# Qwiic_PT100.net
KiCad netlist of a schematic drawn in EAGLE
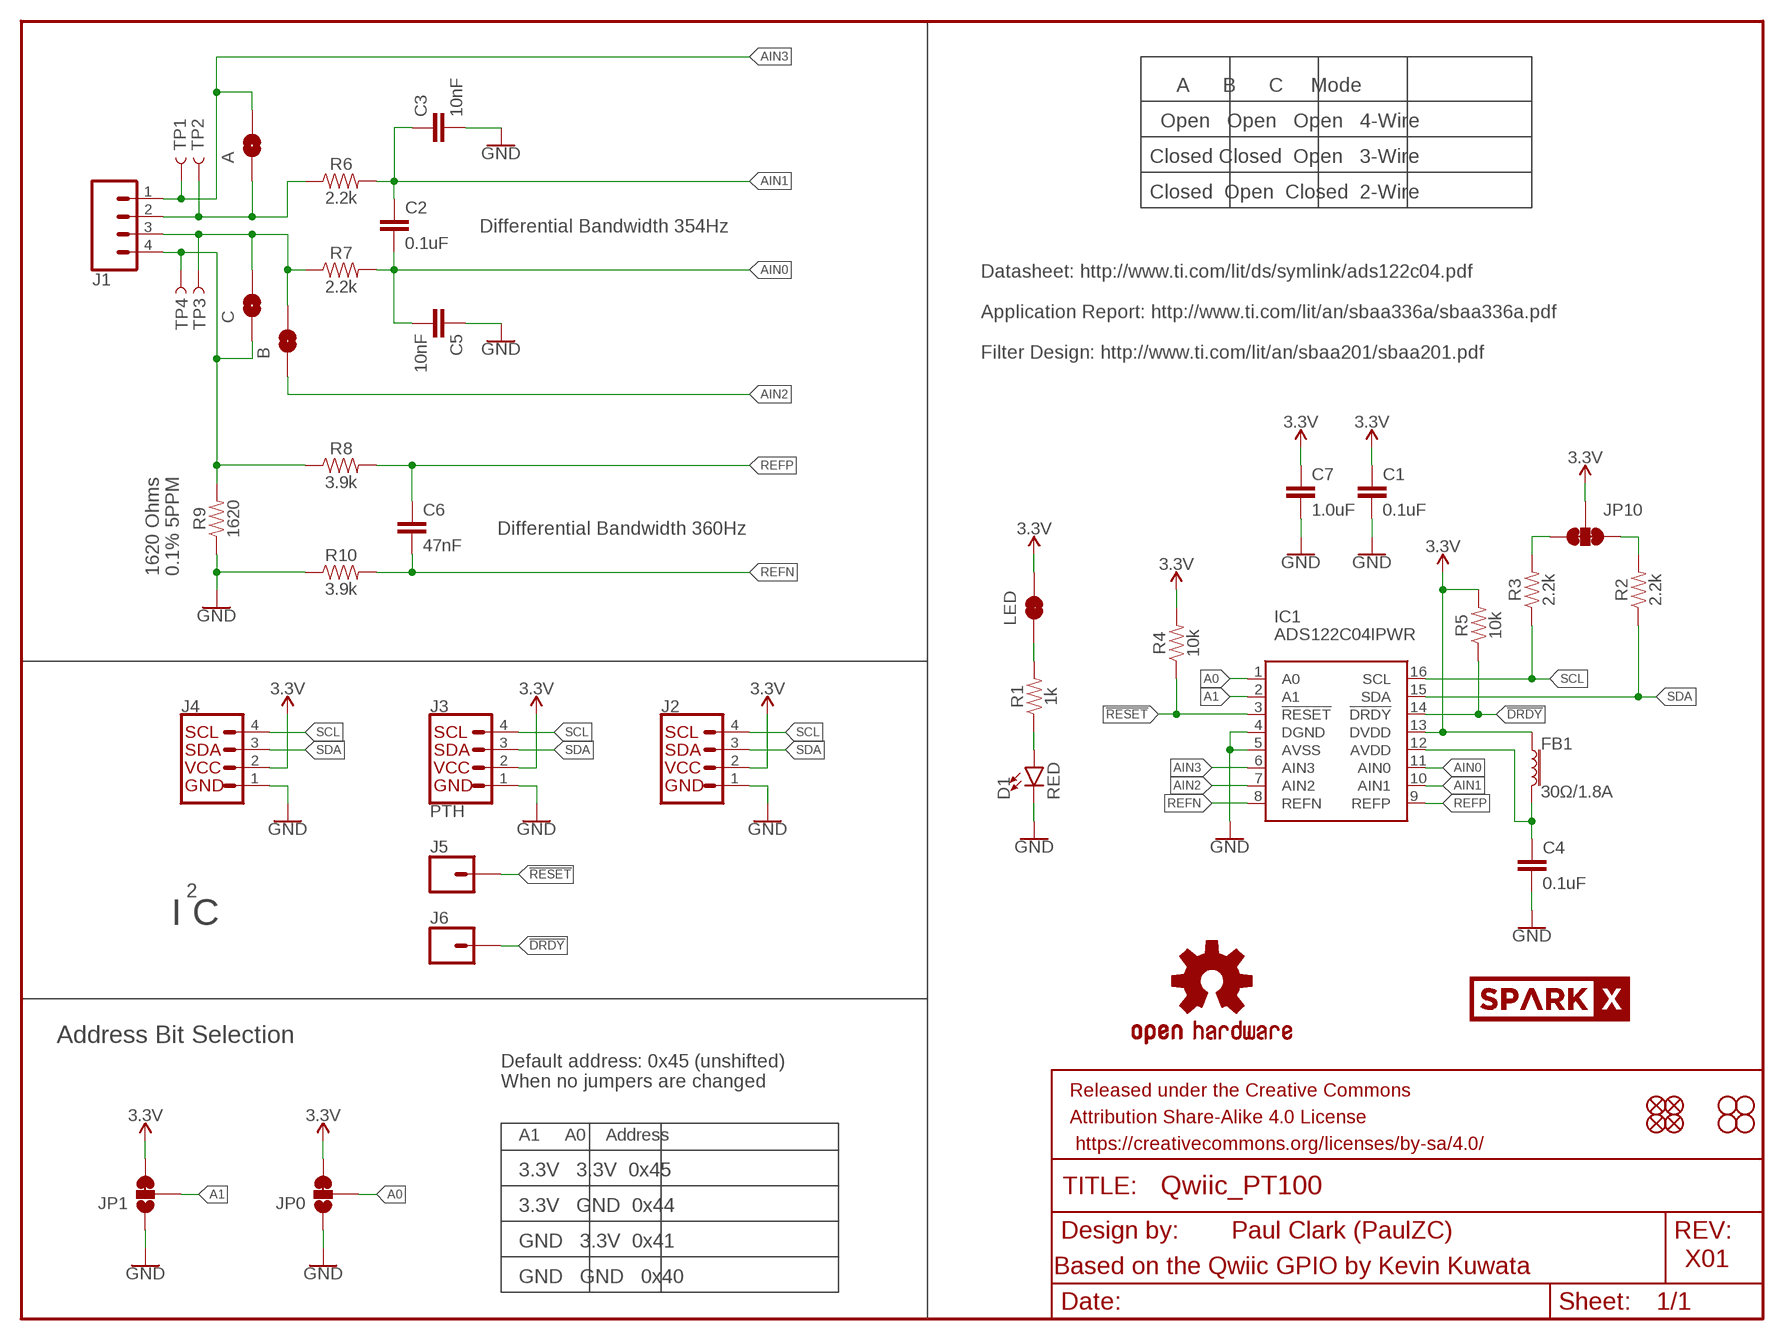
[diagram p0: schematic, sheet 1]

(export (version "E")
  (design (tool "Eeschema 10.0.6"))
  (components
    (comp (ref "A")
      (value "JUMPER-SMT_2_NO_SILK_ROUND")
      (footprint "eagle-import:SMT-JUMPER_2_NO_SILK_ROUND")
      (libsource (lib "eagle-import") (part "JUMPER-SMT_2_NO_SILK_ROUND"))
    )
    (comp (ref "B")
      (value "JUMPER-SMT_2_NO_SILK_ROUND")
      (footprint "eagle-import:SMT-JUMPER_2_NO_SILK_ROUND")
      (libsource (lib "eagle-import") (part "JUMPER-SMT_2_NO_SILK_ROUND"))
    )
    (comp (ref "C")
      (value "JUMPER-SMT_2_NO_SILK_ROUND")
      (footprint "eagle-import:SMT-JUMPER_2_NO_SILK_ROUND")
      (libsource (lib "eagle-import") (part "JUMPER-SMT_2_NO_SILK_ROUND"))
    )
    (comp (ref "C1")
      (value "0.1uF")
      (footprint "eagle-import:0603")
      (libsource (lib "eagle-import") (part "0.1UF-0603-25V-(+80/-20%)"))
    )
    (comp (ref "C2")
      (value "0.1uF")
      (footprint "eagle-import:0603")
      (libsource (lib "eagle-import") (part "0.1UF-0603-25V-5%"))
    )
    (comp (ref "C3")
      (value "10nF")
      (footprint "eagle-import:0603")
      (libsource (lib "eagle-import") (part "10NF-0603-50V-10%"))
    )
    (comp (ref "C4")
      (value "0.1uF")
      (footprint "eagle-import:0603")
      (libsource (lib "eagle-import") (part "0.1UF-0603-25V-(+80/-20%)"))
    )
    (comp (ref "C5")
      (value "10nF")
      (footprint "eagle-import:0603")
      (libsource (lib "eagle-import") (part "10NF-0603-50V-10%"))
    )
    (comp (ref "C6")
      (value "47nF")
      (footprint "eagle-import:0603")
      (libsource (lib "eagle-import") (part "47NF-0603-25V-5%"))
    )
    (comp (ref "C7")
      (value "1.0uF")
      (footprint "eagle-import:0603")
      (libsource (lib "eagle-import") (part "1.0UF-0603-16V-10%-X7R"))
    )
    (comp (ref "D1")
      (value "RED")
      (footprint "eagle-import:LED-0603")
      (libsource (lib "eagle-import") (part "LED-RED0603"))
    )
    (comp (ref "FB1")
      (value "30Ω/1.8A")
      (footprint "eagle-import:0603")
      (libsource (lib "eagle-import") (part "FERRITE_BEAD-0603"))
    )
    (comp (ref "FD1")
      (value "FIDUCIAL1X2")
      (footprint "eagle-import:FIDUCIAL-1X2")
      (libsource (lib "eagle-import") (part "FIDUCIAL1X2"))
    )
    (comp (ref "FD2")
      (value "FIDUCIAL1X2")
      (footprint "eagle-import:FIDUCIAL-1X2")
      (libsource (lib "eagle-import") (part "FIDUCIAL1X2"))
    )
    (comp (ref "FRAME1")
      (value "FRAME-LETTER")
      (footprint "eagle-import:CREATIVE_COMMONS")
      (libsource (lib "eagle-import") (part "FRAME-LETTER"))
    )
    (comp (ref "H1")
      (value "STAND-OFF")
      (footprint "eagle-import:STAND-OFF")
      (libsource (lib "eagle-import") (part "STAND-OFF"))
    )
    (comp (ref "H2")
      (value "STAND-OFF")
      (footprint "eagle-import:STAND-OFF")
      (libsource (lib "eagle-import") (part "STAND-OFF"))
    )
    (comp (ref "IC1")
      (value "ADS122C04IPWR")
      (footprint "eagle-import:SOP65P640X120-16N")
      (fields (field (name "MOUSER_PART_NUMBER") "595-ADS122C04IPWR"))
      (libsource (lib "eagle-import") (part "ADS122C04IPWR"))
    )
    (comp (ref "J1")
      (value "CONN_04LATCH")
      (footprint "eagle-import:LATCHTERMINAL-5MM-4")
      (fields (field (name "PROD_ID") "CON-14722"))
      (libsource (lib "eagle-import") (part "CONN_04LATCH"))
    )
    (comp (ref "J2")
      (value "QWIIC_RIGHT_ANGLE")
      (footprint "eagle-import:JST04_1MM_RA")
      (fields (field (name "PROD_ID") "CONN-13694"))
      (libsource (lib "eagle-import") (part "QWIIC_CONNECTORJS-1MM"))
    )
    (comp (ref "J3")
      (value "PTH")
      (footprint "eagle-import:1X04_NO_SILK")
      (libsource (lib "eagle-import") (part "I2C_STANDARD_NO_SILK"))
    )
    (comp (ref "J4")
      (value "QWIIC_RIGHT_ANGLE")
      (footprint "eagle-import:JST04_1MM_RA")
      (fields (field (name "PROD_ID") "CONN-13694"))
      (libsource (lib "eagle-import") (part "QWIIC_CONNECTORJS-1MM"))
    )
    (comp (ref "J5")
      (value "CONN_01PTH_NO_SILK_YES_STOP")
      (footprint "eagle-import:1X01_NO_SILK")
      (libsource (lib "eagle-import") (part "CONN_01PTH_NO_SILK_YES_STOP"))
    )
    (comp (ref "J6")
      (value "CONN_01PTH_NO_SILK_YES_STOP")
      (footprint "eagle-import:1X01_NO_SILK")
      (libsource (lib "eagle-import") (part "CONN_01PTH_NO_SILK_YES_STOP"))
    )
    (comp (ref "JP0")
      (value "JUMPER-SMT_3_1-NC_TRACE_SILK")
      (footprint "eagle-import:SMT-JUMPER_3_1-NC_TRACE_SILK")
      (libsource (lib "eagle-import") (part "JUMPER-SMT_3_1-NC_TRACE_SILK"))
    )
    (comp (ref "JP1")
      (value "JUMPER-SMT_3_1-NC_TRACE_SILK")
      (footprint "eagle-import:SMT-JUMPER_3_1-NC_TRACE_SILK")
      (libsource (lib "eagle-import") (part "JUMPER-SMT_3_1-NC_TRACE_SILK"))
    )
    (comp (ref "JP2")
      (value "FIDUCIAL1X2")
      (footprint "eagle-import:FIDUCIAL-1X2")
      (libsource (lib "eagle-import") (part "FIDUCIAL1X2"))
    )
    (comp (ref "JP3")
      (value "STAND-OFF")
      (footprint "eagle-import:STAND-OFF")
      (libsource (lib "eagle-import") (part "STAND-OFF"))
    )
    (comp (ref "JP4")
      (value "STAND-OFF")
      (footprint "eagle-import:STAND-OFF")
      (libsource (lib "eagle-import") (part "STAND-OFF"))
    )
    (comp (ref "JP6")
      (value "FIDUCIAL1X2")
      (footprint "eagle-import:FIDUCIAL-1X2")
      (libsource (lib "eagle-import") (part "FIDUCIAL1X2"))
    )
    (comp (ref "JP10")
      (value "JUMPER-SMT_3_2-NC_TRACE_SILK")
      (footprint "eagle-import:SMT-JUMPER_3_2-NC_TRACE_SILK")
      (libsource (lib "eagle-import") (part "JUMPER-SMT_3_2-NC_TRACE_SILK"))
    )
    (comp (ref "LED")
      (value "JUMPER-SMT_2_NC_TRACE_SILK")
      (footprint "eagle-import:SMT-JUMPER_2_NC_TRACE_SILK")
      (libsource (lib "eagle-import") (part "JUMPER-SMT_2_NC_TRACE_SILK"))
    )
    (comp (ref "LOGO1")
      (value "OSHW-LOGOMINI")
      (footprint "eagle-import:OSHW-LOGO-MINI")
      (libsource (lib "eagle-import") (part "OSHW-LOGOMINI"))
    )
    (comp (ref "R1")
      (value "1k")
      (footprint "eagle-import:0603")
      (libsource (lib "eagle-import") (part "1KOHM-0603-1/10W-1%"))
    )
    (comp (ref "R2")
      (value "2.2k")
      (footprint "eagle-import:0603")
      (libsource (lib "eagle-import") (part "2.2KOHM-0603-1/10W-1%"))
    )
    (comp (ref "R3")
      (value "2.2k")
      (footprint "eagle-import:0603")
      (libsource (lib "eagle-import") (part "2.2KOHM-0603-1/10W-1%"))
    )
    (comp (ref "R4")
      (value "10k")
      (footprint "eagle-import:0603")
      (libsource (lib "eagle-import") (part "10KOHM-0603-1/10W-1%"))
    )
    (comp (ref "R5")
      (value "10k")
      (footprint "eagle-import:0603")
      (libsource (lib "eagle-import") (part "10KOHM-0603-1/10W-1%"))
    )
    (comp (ref "R6")
      (value "2.2k")
      (footprint "eagle-import:0603")
      (libsource (lib "eagle-import") (part "2.2KOHM-0603-1/10W-1%"))
    )
    (comp (ref "R7")
      (value "2.2k")
      (footprint "eagle-import:0603")
      (libsource (lib "eagle-import") (part "2.2KOHM-0603-1/10W-1%"))
    )
    (comp (ref "R8")
      (value "3.9k")
      (footprint "eagle-import:0603")
      (libsource (lib "eagle-import") (part "3.9KOHM-0603-1/10W-1%"))
    )
    (comp (ref "R9")
      (value "1620")
      (footprint "eagle-import:0603")
      (libsource (lib "eagle-import") (part "1620OHM-0603-0.1%-5PPM"))
    )
    (comp (ref "R10")
      (value "3.9k")
      (footprint "eagle-import:0603")
      (libsource (lib "eagle-import") (part "3.9KOHM-0603-1/10W-1%"))
    )
    (comp (ref "TP1")
      (value "TEST-POINTTP_15TH_THRU")
      (footprint "eagle-import:TP_15TH")
      (libsource (lib "eagle-import") (part "TEST-POINTTP_15TH_THRU"))
    )
    (comp (ref "TP2")
      (value "TEST-POINTTP_15TH_THRU")
      (footprint "eagle-import:TP_15TH")
      (libsource (lib "eagle-import") (part "TEST-POINTTP_15TH_THRU"))
    )
    (comp (ref "TP3")
      (value "TEST-POINTTP_15TH_THRU")
      (footprint "eagle-import:TP_15TH")
      (libsource (lib "eagle-import") (part "TEST-POINTTP_15TH_THRU"))
    )
    (comp (ref "TP4")
      (value "TEST-POINTTP_15TH_THRU")
      (footprint "eagle-import:TP_15TH")
      (libsource (lib "eagle-import") (part "TEST-POINTTP_15TH_THRU"))
    )
    (comp (ref "U$1")
      (value "SPARKX-LOGO3")
      (footprint "eagle-import:SPARKX-SMALL")
      (libsource (lib "eagle-import") (part "SPARKX-LOGO3"))
    )
    (comp (ref "U$2")
      (value "SPARKX-LOGO3")
      (footprint "eagle-import:SPARKX-SMALL")
      (libsource (lib "eagle-import") (part "SPARKX-LOGO3"))
    )
  )
  (nets
    (net (code "1") (name "/~{DRDY}") (class "Default")
      (node (ref "IC1") (pin "14") (pinfunction "~{DRDY}_14") (pintype "output"))
      (node (ref "J6") (pin "1") (pinfunction "1_1") (pintype "passive"))
      (node (ref "R5") (pin "1") (pinfunction "1_1") (pintype "passive"))
    )
    (net (code "2") (name "/~{RESET}") (class "Default")
      (node (ref "IC1") (pin "3") (pinfunction "~{RESET}_3") (pintype "input"))
      (node (ref "J5") (pin "1") (pinfunction "1_1") (pintype "passive"))
      (node (ref "R4") (pin "1") (pinfunction "1_1") (pintype "passive"))
    )
    (net (code "3") (name "3.3V") (class "Default")
      (node (ref "C1") (pin "1") (pinfunction "1_1") (pintype "passive"))
      (node (ref "C7") (pin "1") (pinfunction "1_1") (pintype "passive"))
      (node (ref "FB1") (pin "1") (pinfunction "1_1") (pintype "passive"))
      (node (ref "IC1") (pin "13") (pinfunction "DVDD_13") (pintype "power_in"))
      (node (ref "J2") (pin "2") (pinfunction "2_2") (pintype "power_in"))
      (node (ref "J3") (pin "2") (pinfunction "2_2") (pintype "power_in"))
      (node (ref "J4") (pin "2") (pinfunction "2_2") (pintype "power_in"))
      (node (ref "JP0") (pin "3") (pinfunction "3_3") (pintype "passive"))
      (node (ref "JP1") (pin "3") (pinfunction "3_3") (pintype "passive"))
      (node (ref "JP10") (pin "2") (pinfunction "2_2") (pintype "passive"))
      (node (ref "LED") (pin "2") (pinfunction "2_2") (pintype "passive"))
      (node (ref "R4") (pin "2") (pinfunction "2_2") (pintype "passive"))
      (node (ref "R5") (pin "2") (pinfunction "2_2") (pintype "passive"))
    )
    (net (code "4") (name "A0") (class "Default")
      (node (ref "IC1") (pin "1") (pinfunction "A0_1") (pintype "input"))
      (node (ref "JP0") (pin "2") (pinfunction "2_2") (pintype "passive"))
    )
    (net (code "5") (name "A1") (class "Default")
      (node (ref "IC1") (pin "2") (pinfunction "A1_2") (pintype "input"))
      (node (ref "JP1") (pin "2") (pinfunction "2_2") (pintype "passive"))
    )
    (net (code "6") (name "AIN0") (class "Default")
      (node (ref "C2") (pin "2") (pinfunction "2_2") (pintype "passive"))
      (node (ref "C5") (pin "2") (pinfunction "2_2") (pintype "passive"))
      (node (ref "IC1") (pin "11") (pinfunction "AIN0_11") (pintype "input"))
      (node (ref "R7") (pin "2") (pinfunction "2_2") (pintype "passive"))
    )
    (net (code "7") (name "AIN1") (class "Default")
      (node (ref "C2") (pin "1") (pinfunction "1_1") (pintype "passive"))
      (node (ref "C3") (pin "1") (pinfunction "1_1") (pintype "passive"))
      (node (ref "IC1") (pin "10") (pinfunction "AIN1_10") (pintype "input"))
      (node (ref "R6") (pin "2") (pinfunction "2_2") (pintype "passive"))
    )
    (net (code "8") (name "AIN2") (class "Default")
      (node (ref "B") (pin "1") (pinfunction "1_1") (pintype "passive"))
      (node (ref "IC1") (pin "7") (pinfunction "AIN2_7") (pintype "input"))
    )
    (net (code "9") (name "AIN3") (class "Default")
      (node (ref "A") (pin "2") (pinfunction "2_2") (pintype "passive"))
      (node (ref "IC1") (pin "6") (pinfunction "AIN3_6") (pintype "input"))
      (node (ref "J1") (pin "1") (pinfunction "1_1") (pintype "passive"))
      (node (ref "TP1") (pin "P$1") (pinfunction "1_P$1") (pintype "bidirectional"))
    )
    (net (code "10") (name "GND") (class "Default")
      (node (ref "C1") (pin "2") (pinfunction "2_2") (pintype "passive"))
      (node (ref "C3") (pin "2") (pinfunction "2_2") (pintype "passive"))
      (node (ref "C4") (pin "2") (pinfunction "2_2") (pintype "passive"))
      (node (ref "C5") (pin "1") (pinfunction "1_1") (pintype "passive"))
      (node (ref "C7") (pin "2") (pinfunction "2_2") (pintype "passive"))
      (node (ref "D1") (pin "C") (pinfunction "C_C") (pintype "passive"))
      (node (ref "IC1") (pin "4") (pinfunction "DGND_4") (pintype "power_in"))
      (node (ref "IC1") (pin "5") (pinfunction "AVSS_5") (pintype "power_in"))
      (node (ref "J2") (pin "1") (pinfunction "1_1") (pintype "power_in"))
      (node (ref "J3") (pin "1") (pinfunction "1_1") (pintype "power_in"))
      (node (ref "J4") (pin "1") (pinfunction "1_1") (pintype "power_in"))
      (node (ref "JP0") (pin "1") (pinfunction "1_1") (pintype "passive"))
      (node (ref "JP1") (pin "1") (pinfunction "1_1") (pintype "passive"))
      (node (ref "R10") (pin "1") (pinfunction "1_1") (pintype "passive"))
      (node (ref "R9") (pin "1") (pinfunction "1_1") (pintype "passive"))
    )
    (net (code "11") (name "Net-(D1-PadA)") (class "Default")
      (node (ref "D1") (pin "A") (pinfunction "A_A") (pintype "passive"))
      (node (ref "R1") (pin "1") (pinfunction "1_1") (pintype "passive"))
    )
    (net (code "12") (name "Net-(IC1-AVDD)") (class "Default")
      (node (ref "C4") (pin "1") (pinfunction "1_1") (pintype "passive"))
      (node (ref "FB1") (pin "2") (pinfunction "2_2") (pintype "passive"))
      (node (ref "IC1") (pin "12") (pinfunction "AVDD_12") (pintype "power_in"))
    )
    (net (code "13") (name "Net-(JP10-Pad1)") (class "Default")
      (node (ref "JP10") (pin "1") (pinfunction "1_1") (pintype "passive"))
      (node (ref "R2") (pin "2") (pinfunction "2_2") (pintype "passive"))
    )
    (net (code "14") (name "Net-(JP10-Pad3)") (class "Default")
      (node (ref "JP10") (pin "3") (pinfunction "3_3") (pintype "passive"))
      (node (ref "R3") (pin "2") (pinfunction "2_2") (pintype "passive"))
    )
    (net (code "15") (name "Net-(LED-Pad1)") (class "Default")
      (node (ref "LED") (pin "1") (pinfunction "1_1") (pintype "passive"))
      (node (ref "R1") (pin "2") (pinfunction "2_2") (pintype "passive"))
    )
    (net (code "16") (name "Net-(TP2-1)") (class "Default")
      (node (ref "A") (pin "1") (pinfunction "1_1") (pintype "passive"))
      (node (ref "J1") (pin "2") (pinfunction "2_2") (pintype "passive"))
      (node (ref "R6") (pin "1") (pinfunction "1_1") (pintype "passive"))
      (node (ref "TP2") (pin "P$1") (pinfunction "1_P$1") (pintype "bidirectional"))
    )
    (net (code "17") (name "Net-(TP3-1)") (class "Default")
      (node (ref "B") (pin "2") (pinfunction "2_2") (pintype "passive"))
      (node (ref "C") (pin "2") (pinfunction "2_2") (pintype "passive"))
      (node (ref "J1") (pin "3") (pinfunction "3_3") (pintype "passive"))
      (node (ref "R7") (pin "1") (pinfunction "1_1") (pintype "passive"))
      (node (ref "TP3") (pin "P$1") (pinfunction "1_P$1") (pintype "bidirectional"))
    )
    (net (code "18") (name "Net-(TP4-1)") (class "Default")
      (node (ref "C") (pin "1") (pinfunction "1_1") (pintype "passive"))
      (node (ref "J1") (pin "4") (pinfunction "4_4") (pintype "passive"))
      (node (ref "R8") (pin "1") (pinfunction "1_1") (pintype "passive"))
      (node (ref "R9") (pin "2") (pinfunction "2_2") (pintype "passive"))
      (node (ref "TP4") (pin "P$1") (pinfunction "1_P$1") (pintype "bidirectional"))
    )
    (net (code "19") (name "REFN") (class "Default")
      (node (ref "C6") (pin "2") (pinfunction "2_2") (pintype "passive"))
      (node (ref "IC1") (pin "8") (pinfunction "REFN_8") (pintype "input"))
      (node (ref "R10") (pin "2") (pinfunction "2_2") (pintype "passive"))
    )
    (net (code "20") (name "REFP") (class "Default")
      (node (ref "C6") (pin "1") (pinfunction "1_1") (pintype "passive"))
      (node (ref "IC1") (pin "9") (pinfunction "REFP_9") (pintype "input"))
      (node (ref "R8") (pin "2") (pinfunction "2_2") (pintype "passive"))
    )
    (net (code "21") (name "SCL") (class "Default")
      (node (ref "IC1") (pin "16") (pinfunction "SCL_16") (pintype "bidirectional"))
      (node (ref "J2") (pin "4") (pinfunction "4_4") (pintype "passive"))
      (node (ref "J3") (pin "4") (pinfunction "4_4") (pintype "passive"))
      (node (ref "J4") (pin "4") (pinfunction "4_4") (pintype "passive"))
      (node (ref "R3") (pin "1") (pinfunction "1_1") (pintype "passive"))
    )
    (net (code "22") (name "SDA") (class "Default")
      (node (ref "IC1") (pin "15") (pinfunction "SDA_15") (pintype "bidirectional"))
      (node (ref "J2") (pin "3") (pinfunction "3_3") (pintype "passive"))
      (node (ref "J3") (pin "3") (pinfunction "3_3") (pintype "passive"))
      (node (ref "J4") (pin "3") (pinfunction "3_3") (pintype "passive"))
      (node (ref "R2") (pin "1") (pinfunction "1_1") (pintype "passive"))
    )
  )
)
